# 1_Power.net
KiCad netlist of a schematic drawn in Altium Designer
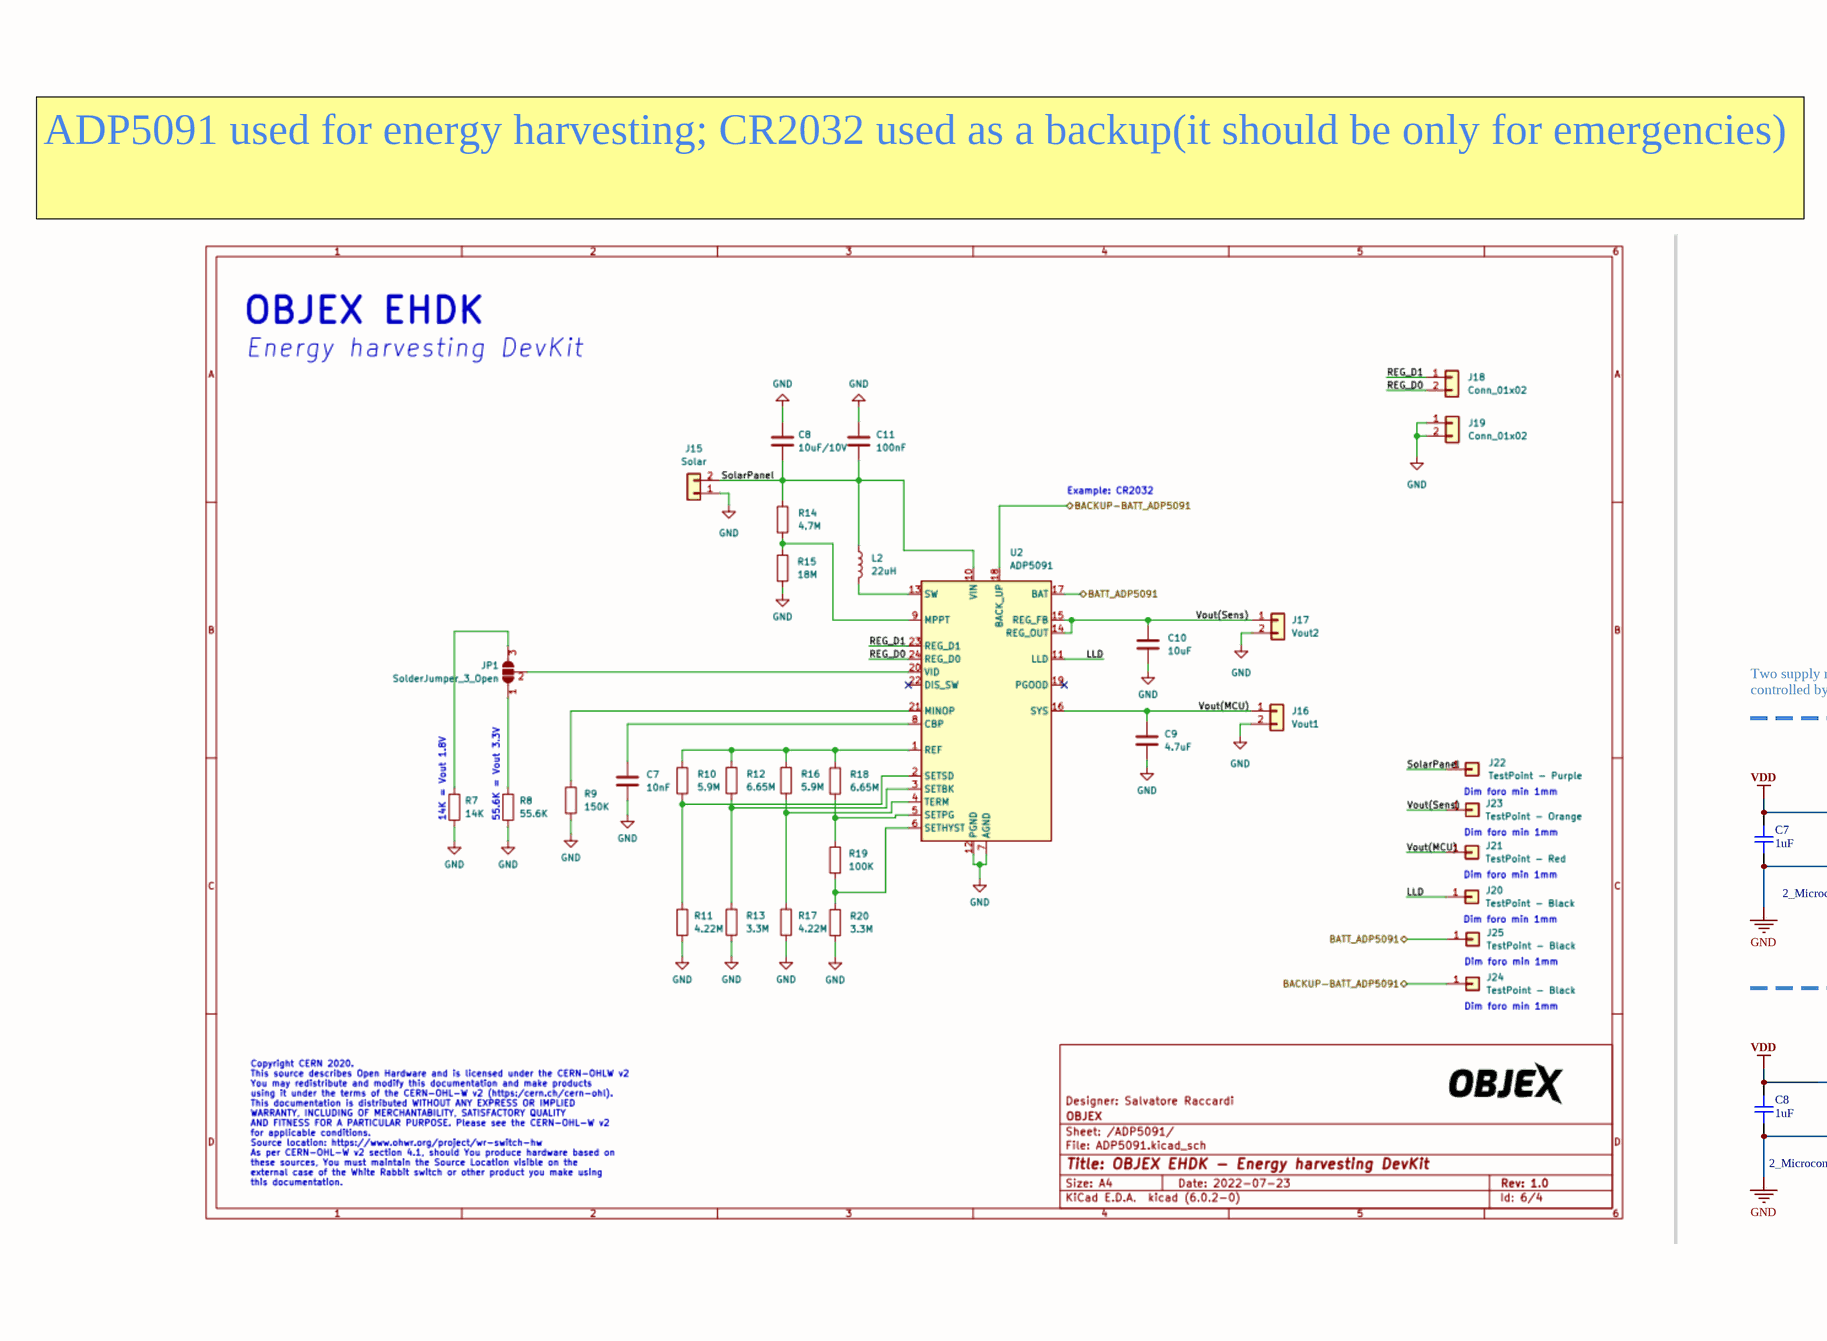
[diagram p0: 1_Power.SchDoc, left]
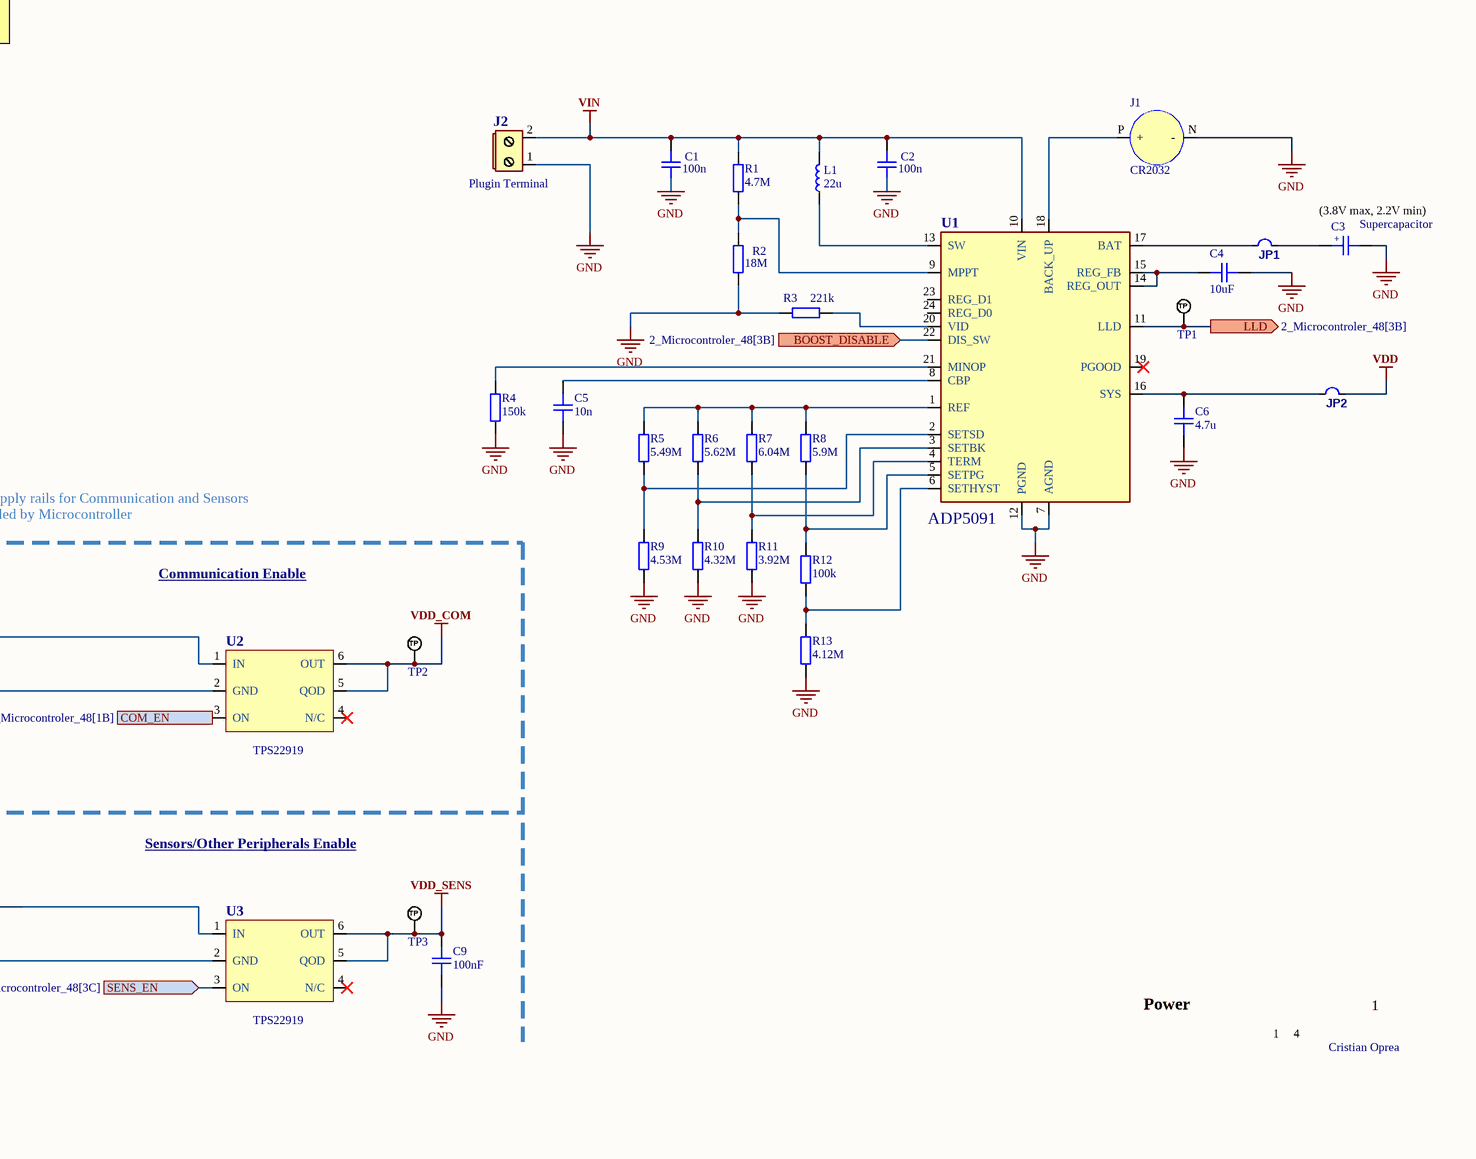
[diagram p1: 1_Power.SchDoc, middle]
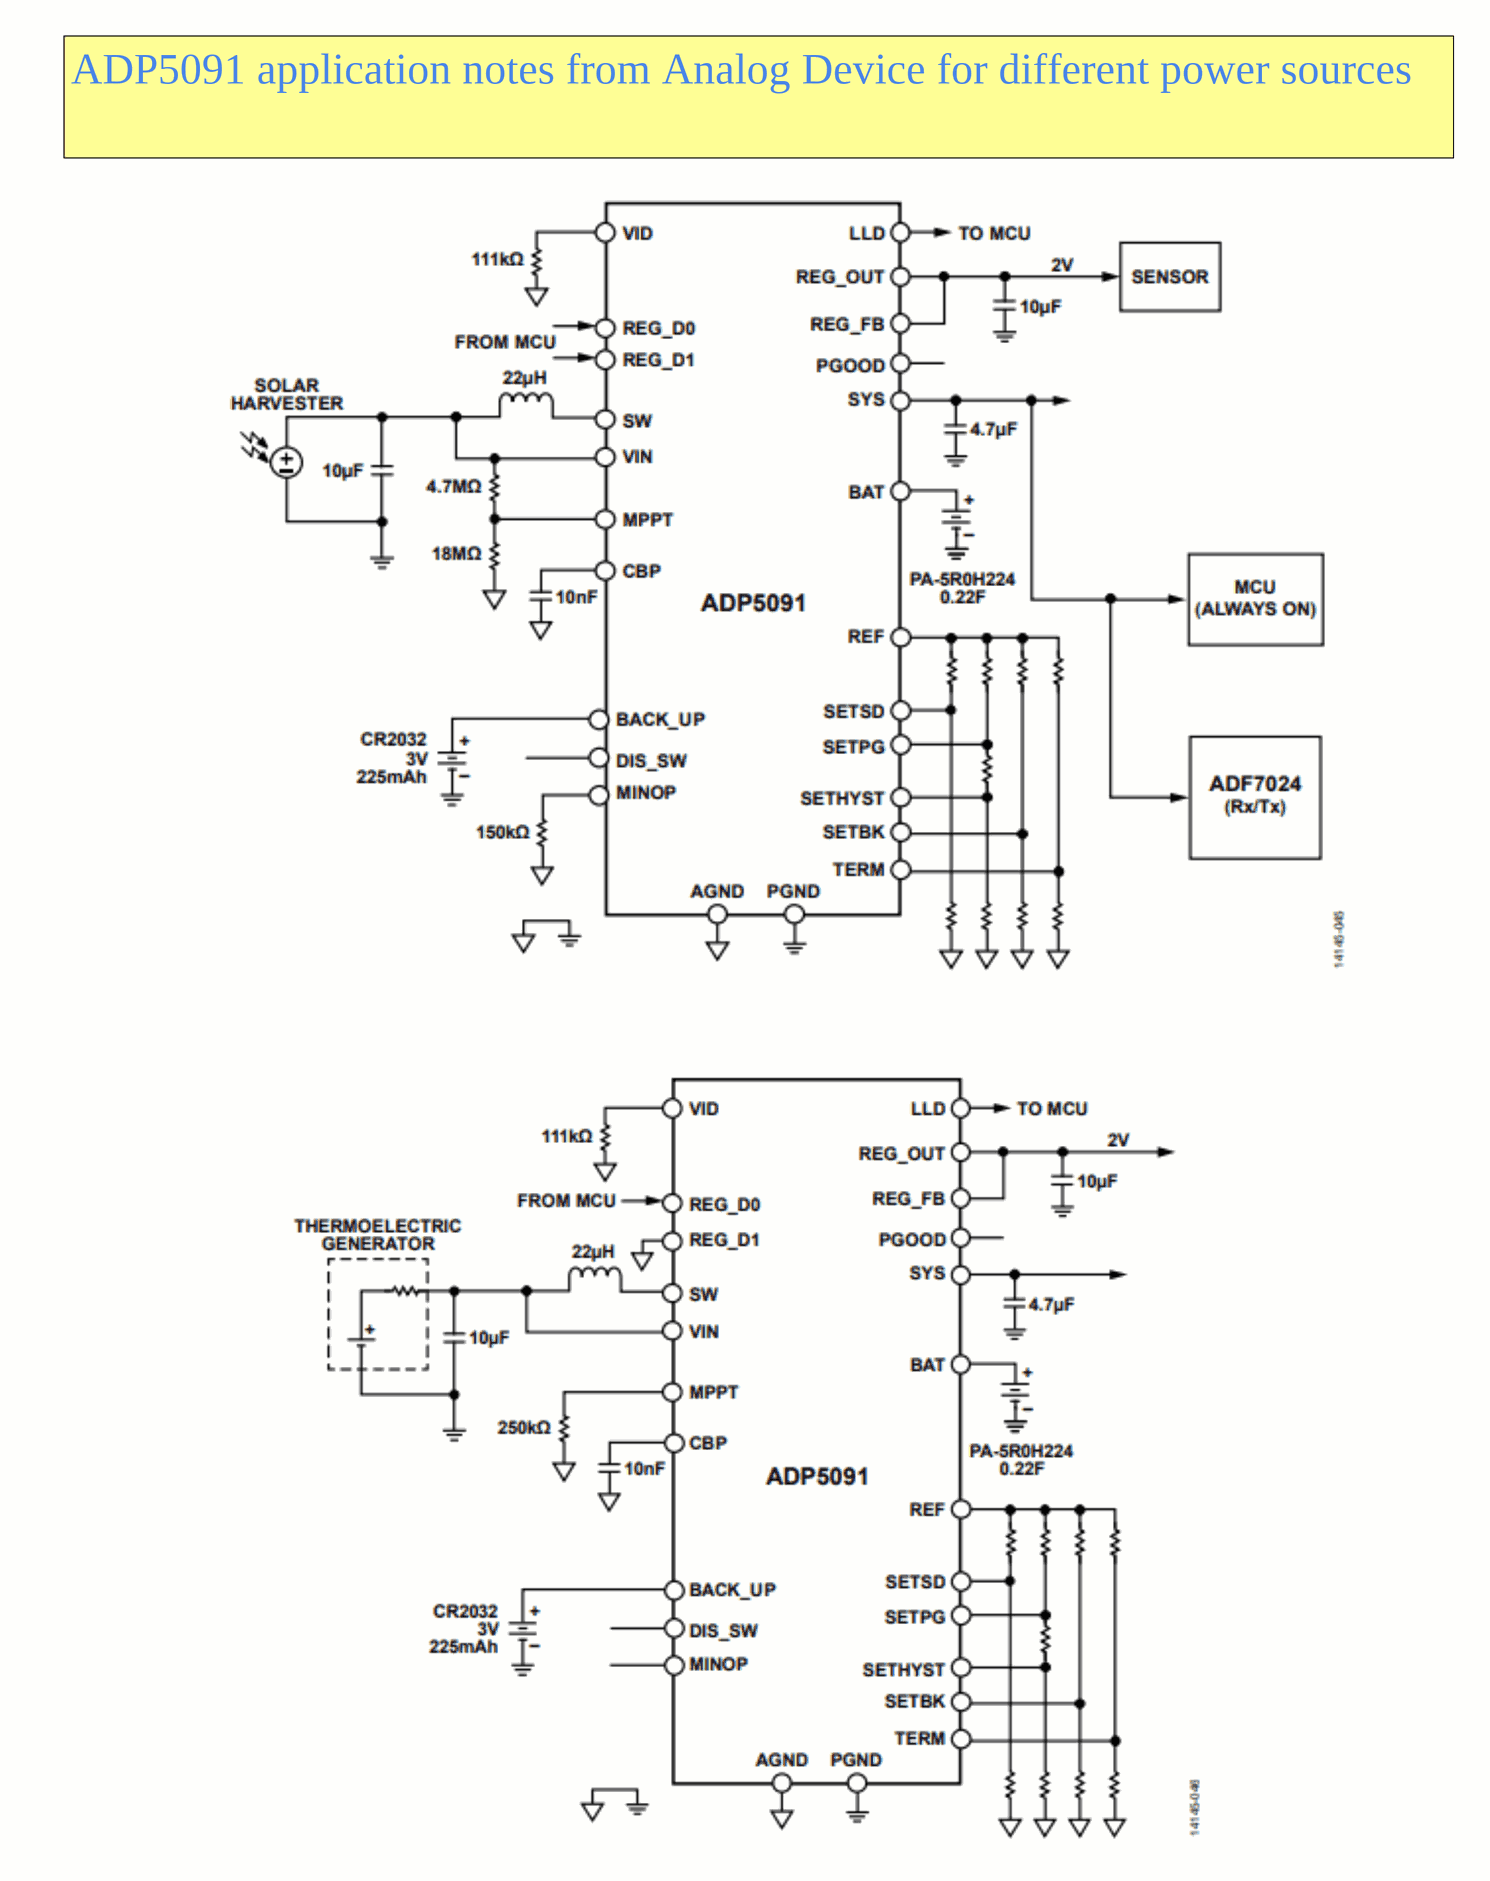
[diagram p2: 1_Power.SchDoc, right]

(export (version "E")
  (design (tool "Eeschema 10.0.6"))
  (components
    (comp (ref "C1")
      (value "100n")
      (footprint "C0603")
      (description "Capacitor SMD 0603")
      (libsource (lib "Schlib_H2") (part "CAP_0603"))
    )
    (comp (ref "C2")
      (value "100n")
      (footprint "C0603")
      (description "Capacitor SMD 0603")
      (libsource (lib "Schlib_H2") (part "CAP_0603"))
    )
    (comp (ref "C3")
      (value "Supercapacitor")
      (footprint "CAP_POL_8x16x3.5")
      (libsource (lib "Schlib_H2") (part "Supercapacitor"))
    )
    (comp (ref "C4")
      (value "10uF")
      (footprint "C0805")
      (description "Capacitor SMD 0805")
      (libsource (lib "Schlib_H2") (part "CAP_0805"))
    )
    (comp (ref "C5")
      (value "10n")
      (footprint "C0603")
      (description "Capacitor SMD 0603")
      (libsource (lib "Schlib_H2") (part "CAP_0603"))
    )
    (comp (ref "C6")
      (value "4.7u")
      (footprint "C0603")
      (description "Capacitor SMD 0603")
      (libsource (lib "Schlib_H2") (part "CAP_0603"))
    )
    (comp (ref "C7")
      (value "1uF")
      (footprint "C0603")
      (description "Capacitor SMD 0603")
      (libsource (lib "Schlib_H2") (part "CAP_0603"))
    )
    (comp (ref "C8")
      (value "1uF")
      (footprint "C0603")
      (description "Capacitor SMD 0603")
      (libsource (lib "Schlib_H2") (part "CAP_0603"))
    )
    (comp (ref "C9")
      (value "100nF")
      (footprint "C0603")
      (description "Capacitor SMD 0603")
      (libsource (lib "Schlib_H2") (part "CAP_0603"))
    )
    (comp (ref "J1")
      (value "CR2032")
      (footprint "BAT_CR2032-BS-6-1")
      (description "CR2032 Coin Cell Battery Holder")
      (fields (field (name "MANUFACTURER") "Q&J") (field (name "MANUFACTURER PART NUMBER") "CR2032-BS-6-1"))
      (libsource (lib "Schlib_H2") (part "CR2032-BS-6-1"))
    )
    (comp (ref "J2")
      (value "Plugin Terminal")
      (footprint "2.54_pluggable_terminal")
      (description "Screw terminal or plug terminal for power")
      (libsource (lib "Schlib_H2") (part "Power_Connector"))
    )
    (comp (ref "JP1")
      (value "JUMPER")
      (footprint "HEADER_1x2_2.54")
      (libsource (lib "Schlib_H2") (part "JUMPER"))
    )
    (comp (ref "JP2")
      (value "JUMPER")
      (footprint "HEADER_1x2_2.54")
      (libsource (lib "Schlib_H2") (part "JUMPER"))
    )
    (comp (ref "L1")
      (value "22u")
      (footprint "IND_3.2_4")
      (description "Inductor SMD 1008")
      (libsource (lib "Schlib_H2") (part "IND_1008"))
    )
    (comp (ref "R1")
      (value "4.7M")
      (footprint "R0603")
      (description "Resistor SMD 0603")
      (libsource (lib "Schlib_H2") (part "RES_0603"))
    )
    (comp (ref "R2")
      (value "18M")
      (footprint "R0603")
      (description "Resistor SMD 0603")
      (libsource (lib "Schlib_H2") (part "RES_0603"))
    )
    (comp (ref "R3")
      (value "221k")
      (footprint "R0603")
      (description "Resistor SMD 0603")
      (libsource (lib "Schlib_H2") (part "RES_0603"))
    )
    (comp (ref "R4")
      (value "150k")
      (footprint "R0603")
      (description "Resistor SMD 0603")
      (libsource (lib "Schlib_H2") (part "RES_0603"))
    )
    (comp (ref "R5")
      (value "5.49M")
      (footprint "R0603")
      (description "Resistor SMD 0603")
      (libsource (lib "Schlib_H2") (part "RES_0603"))
    )
    (comp (ref "R6")
      (value "5.62M")
      (footprint "R0603")
      (description "Resistor SMD 0603")
      (libsource (lib "Schlib_H2") (part "RES_0603"))
    )
    (comp (ref "R7")
      (value "6.04M")
      (footprint "R0603")
      (description "Resistor SMD 0603")
      (libsource (lib "Schlib_H2") (part "RES_0603"))
    )
    (comp (ref "R8")
      (value "5.9M")
      (footprint "R0603")
      (description "Resistor SMD 0603")
      (libsource (lib "Schlib_H2") (part "RES_0603"))
    )
    (comp (ref "R9")
      (value "4.53M")
      (footprint "R0603")
      (description "Resistor SMD 0603")
      (libsource (lib "Schlib_H2") (part "RES_0603"))
    )
    (comp (ref "R10")
      (value "4.32M")
      (footprint "R0603")
      (description "Resistor SMD 0603")
      (libsource (lib "Schlib_H2") (part "RES_0603"))
    )
    (comp (ref "R11")
      (value "3.92M")
      (footprint "R0603")
      (description "Resistor SMD 0603")
      (libsource (lib "Schlib_H2") (part "RES_0603"))
    )
    (comp (ref "R12")
      (value "100k")
      (footprint "R0603")
      (description "Resistor SMD 0603")
      (libsource (lib "Schlib_H2") (part "RES_0603"))
    )
    (comp (ref "R13")
      (value "4.12M")
      (footprint "R0603")
      (description "Resistor SMD 0603")
      (libsource (lib "Schlib_H2") (part "RES_0603"))
    )
    (comp (ref "TP1")
      (value "TP_NOBOM")
      (footprint "TEST_PAD_THD")
      (description "Test Point Round 1mm (NO BOM)")
      (libsource (lib "Schlib_H2") (part "TEST_POINT_RND_1MM"))
    )
    (comp (ref "TP2")
      (value "TP_NOBOM")
      (footprint "TEST_PAD_THD")
      (description "Test Point Round 1mm (NO BOM)")
      (libsource (lib "Schlib_H2") (part "TEST_POINT_RND_1MM"))
    )
    (comp (ref "TP3")
      (value "TP_NOBOM")
      (footprint "TEST_PAD_THD")
      (description "Test Point Round 1mm (NO BOM)")
      (libsource (lib "Schlib_H2") (part "TEST_POINT_RND_1MM"))
    )
    (comp (ref "U1")
      (value "ADP5091")
      (footprint "LFCSP-24")
      (description "Ultralow Power Energy Harvester PMUs \r\nwith MPPT and Charge Management and BAckup Supply")
      (libsource (lib "Schlib_H2") (part "ADP5091"))
    )
    (comp (ref "U2")
      (value "TPS22919")
      (footprint "SC70-6")
      (description "5.5-V, 1.5-A, 90-mΩ load switch with adjustable output discharge")
      (libsource (lib "Schlib_H2") (part "TPS22919"))
    )
    (comp (ref "U3")
      (value "TPS22919")
      (footprint "SC70-6")
      (description "5.5-V, 1.5-A, 90-mΩ load switch with adjustable output discharge")
      (libsource (lib "Schlib_H2") (part "TPS22919"))
    )
  )
  (nets
    (net (code "1") (name "/BOOST_DISABLE") (class "Default")
      (node (ref "U1") (pin "22") (pinfunction "DIS_SW_22") (pintype "passive"))
    )
    (net (code "2") (name "/COM_EN") (class "Default")
      (node (ref "U2") (pin "3") (pinfunction "ON_3") (pintype "passive"))
    )
    (net (code "3") (name "/LLD") (class "Default")
      (node (ref "TP1") (pin "1") (pinfunction "TP_1") (pintype "passive"))
      (node (ref "U1") (pin "11") (pinfunction "LLD_11") (pintype "passive"))
    )
    (net (code "4") (name "/SENS_EN") (class "Default")
      (node (ref "U3") (pin "3") (pinfunction "ON_3") (pintype "passive"))
    )
    (net (code "5") (name "GND") (class "Default")
      (node (ref "C1") (pin "1") (pinfunction "1_1") (pintype "passive"))
      (node (ref "C2") (pin "1") (pinfunction "1_1") (pintype "passive"))
      (node (ref "C3") (pin "2") (pinfunction "2_2") (pintype "passive"))
      (node (ref "C4") (pin "2") (pinfunction "2_2") (pintype "passive"))
      (node (ref "C5") (pin "1") (pinfunction "1_1") (pintype "passive"))
      (node (ref "C6") (pin "1") (pinfunction "1_1") (pintype "passive"))
      (node (ref "C7") (pin "1") (pinfunction "1_1") (pintype "passive"))
      (node (ref "C8") (pin "1") (pinfunction "1_1") (pintype "passive"))
      (node (ref "C9") (pin "1") (pinfunction "1_1") (pintype "passive"))
      (node (ref "J1") (pin "N") (pinfunction "-_N") (pintype "passive"))
      (node (ref "J2") (pin "1") (pinfunction "1_1") (pintype "passive"))
      (node (ref "R10") (pin "1") (pinfunction "1_1") (pintype "passive"))
      (node (ref "R11") (pin "1") (pinfunction "1_1") (pintype "passive"))
      (node (ref "R13") (pin "1") (pinfunction "1_1") (pintype "passive"))
      (node (ref "R2") (pin "1") (pinfunction "1_1") (pintype "passive"))
      (node (ref "R3") (pin "1") (pinfunction "1_1") (pintype "passive"))
      (node (ref "R4") (pin "1") (pinfunction "1_1") (pintype "passive"))
      (node (ref "R9") (pin "1") (pinfunction "1_1") (pintype "passive"))
      (node (ref "U1") (pin "12") (pinfunction "PGND_12") (pintype "passive"))
      (node (ref "U1") (pin "7") (pinfunction "AGND_7") (pintype "passive"))
      (node (ref "U2") (pin "2") (pinfunction "GND_2") (pintype "passive"))
      (node (ref "U3") (pin "2") (pinfunction "GND_2") (pintype "passive"))
    )
    (net (code "6") (name "Net-(C3-Pad1)") (class "Default")
      (node (ref "C3") (pin "1") (pinfunction "1_1") (pintype "passive"))
      (node (ref "JP1") (pin "2") (pinfunction "2_2") (pintype "passive"))
    )
    (net (code "7") (name "Net-(J1-+)") (class "Default")
      (node (ref "J1") (pin "P") (pinfunction "+_P") (pintype "passive"))
      (node (ref "U1") (pin "18") (pinfunction "BACK_UP_18") (pintype "passive"))
    )
    (net (code "8") (name "Net-(U1-BAT)") (class "Default")
      (node (ref "JP1") (pin "1") (pinfunction "1_1") (pintype "passive"))
      (node (ref "U1") (pin "17") (pinfunction "BAT_17") (pintype "passive"))
    )
    (net (code "9") (name "Net-(U1-CBP)") (class "Default")
      (node (ref "C5") (pin "2") (pinfunction "2_2") (pintype "passive"))
      (node (ref "U1") (pin "8") (pinfunction "CBP_8") (pintype "passive"))
    )
    (net (code "10") (name "Net-(U1-MINOP)") (class "Default")
      (node (ref "R4") (pin "2") (pinfunction "2_2") (pintype "passive"))
      (node (ref "U1") (pin "21") (pinfunction "MINOP_21") (pintype "passive"))
    )
    (net (code "11") (name "Net-(U1-MPPT)") (class "Default")
      (node (ref "R1") (pin "1") (pinfunction "1_1") (pintype "passive"))
      (node (ref "R2") (pin "2") (pinfunction "2_2") (pintype "passive"))
      (node (ref "U1") (pin "9") (pinfunction "MPPT_9") (pintype "passive"))
    )
    (net (code "12") (name "Net-(U1-REF)") (class "Default")
      (node (ref "R5") (pin "2") (pinfunction "2_2") (pintype "passive"))
      (node (ref "R6") (pin "2") (pinfunction "2_2") (pintype "passive"))
      (node (ref "R7") (pin "2") (pinfunction "2_2") (pintype "passive"))
      (node (ref "R8") (pin "2") (pinfunction "2_2") (pintype "passive"))
      (node (ref "U1") (pin "1") (pinfunction "REF_1") (pintype "passive"))
    )
    (net (code "13") (name "Net-(U1-REG_FB)") (class "Default")
      (node (ref "C4") (pin "1") (pinfunction "1_1") (pintype "passive"))
      (node (ref "U1") (pin "14") (pinfunction "REG_OUT_14") (pintype "passive"))
      (node (ref "U1") (pin "15") (pinfunction "REG_FB_15") (pintype "passive"))
    )
    (net (code "14") (name "Net-(U1-SETBK)") (class "Default")
      (node (ref "R10") (pin "2") (pinfunction "2_2") (pintype "passive"))
      (node (ref "R6") (pin "1") (pinfunction "1_1") (pintype "passive"))
      (node (ref "U1") (pin "3") (pinfunction "SETBK_3") (pintype "passive"))
    )
    (net (code "15") (name "Net-(U1-SETHYST)") (class "Default")
      (node (ref "R12") (pin "1") (pinfunction "1_1") (pintype "passive"))
      (node (ref "R13") (pin "2") (pinfunction "2_2") (pintype "passive"))
      (node (ref "U1") (pin "6") (pinfunction "SETHYST_6") (pintype "passive"))
    )
    (net (code "16") (name "Net-(U1-SETPG)") (class "Default")
      (node (ref "R12") (pin "2") (pinfunction "2_2") (pintype "passive"))
      (node (ref "R8") (pin "1") (pinfunction "1_1") (pintype "passive"))
      (node (ref "U1") (pin "5") (pinfunction "SETPG_5") (pintype "passive"))
    )
    (net (code "17") (name "Net-(U1-SETSD)") (class "Default")
      (node (ref "R5") (pin "1") (pinfunction "1_1") (pintype "passive"))
      (node (ref "R9") (pin "2") (pinfunction "2_2") (pintype "passive"))
      (node (ref "U1") (pin "2") (pinfunction "SETSD_2") (pintype "passive"))
    )
    (net (code "18") (name "Net-(U1-SW)") (class "Default")
      (node (ref "L1") (pin "1") (pinfunction "1_1") (pintype "passive"))
      (node (ref "U1") (pin "13") (pinfunction "SW_13") (pintype "passive"))
    )
    (net (code "19") (name "Net-(U1-SYS)") (class "Default")
      (node (ref "C6") (pin "2") (pinfunction "2_2") (pintype "passive"))
      (node (ref "JP2") (pin "1") (pinfunction "1_1") (pintype "passive"))
      (node (ref "U1") (pin "16") (pinfunction "SYS_16") (pintype "passive"))
    )
    (net (code "20") (name "Net-(U1-TERM)") (class "Default")
      (node (ref "R11") (pin "2") (pinfunction "2_2") (pintype "passive"))
      (node (ref "R7") (pin "1") (pinfunction "1_1") (pintype "passive"))
      (node (ref "U1") (pin "4") (pinfunction "TERM_4") (pintype "passive"))
    )
    (net (code "21") (name "Net-(U1-VID)") (class "Default")
      (node (ref "R3") (pin "2") (pinfunction "2_2") (pintype "passive"))
      (node (ref "U1") (pin "20") (pinfunction "VID_20") (pintype "passive"))
    )
    (net (code "22") (name "VDD") (class "Default")
      (node (ref "C7") (pin "2") (pinfunction "2_2") (pintype "passive"))
      (node (ref "C8") (pin "2") (pinfunction "2_2") (pintype "passive"))
      (node (ref "JP2") (pin "2") (pinfunction "2_2") (pintype "passive"))
      (node (ref "U2") (pin "1") (pinfunction "IN_1") (pintype "passive"))
      (node (ref "U3") (pin "1") (pinfunction "IN_1") (pintype "passive"))
    )
    (net (code "23") (name "VDD_COM") (class "Default")
      (node (ref "TP2") (pin "1") (pinfunction "TP_1") (pintype "passive"))
      (node (ref "U2") (pin "5") (pinfunction "QOD_5") (pintype "passive"))
      (node (ref "U2") (pin "6") (pinfunction "OUT_6") (pintype "passive"))
    )
    (net (code "24") (name "VDD_SENS") (class "Default")
      (node (ref "C9") (pin "2") (pinfunction "2_2") (pintype "passive"))
      (node (ref "TP3") (pin "1") (pinfunction "TP_1") (pintype "passive"))
      (node (ref "U3") (pin "5") (pinfunction "QOD_5") (pintype "passive"))
      (node (ref "U3") (pin "6") (pinfunction "OUT_6") (pintype "passive"))
    )
    (net (code "25") (name "VIN") (class "Default")
      (node (ref "C1") (pin "2") (pinfunction "2_2") (pintype "passive"))
      (node (ref "C2") (pin "2") (pinfunction "2_2") (pintype "passive"))
      (node (ref "J2") (pin "2") (pinfunction "2_2") (pintype "passive"))
      (node (ref "L1") (pin "2") (pinfunction "2_2") (pintype "passive"))
      (node (ref "R1") (pin "2") (pinfunction "2_2") (pintype "passive"))
      (node (ref "U1") (pin "10") (pinfunction "VIN_10") (pintype "passive"))
    )
    (net (code "26") (name "unconnected-(U1-PGOOD-Pad19)") (class "Default")
      (node (ref "U1") (pin "19") (pinfunction "PGOOD_19") (pintype "passive+no_connect"))
    )
    (net (code "27") (name "unconnected-(U1-REG_D0-Pad24)") (class "Default")
      (node (ref "U1") (pin "24") (pinfunction "REG_D0_24") (pintype "passive"))
    )
    (net (code "28") (name "unconnected-(U1-REG_D1-Pad23)") (class "Default")
      (node (ref "U1") (pin "23") (pinfunction "REG_D1_23") (pintype "passive"))
    )
    (net (code "29") (name "unconnected-(U2-N{slash}C-Pad4)") (class "Default")
      (node (ref "U2") (pin "4") (pinfunction "N/C_4") (pintype "passive+no_connect"))
    )
    (net (code "30") (name "unconnected-(U3-N{slash}C-Pad4)") (class "Default")
      (node (ref "U3") (pin "4") (pinfunction "N/C_4") (pintype "passive+no_connect"))
    )
  )
)
